# battery_current-meas.net
KiCad netlist of a schematic drawn in Altium Designer
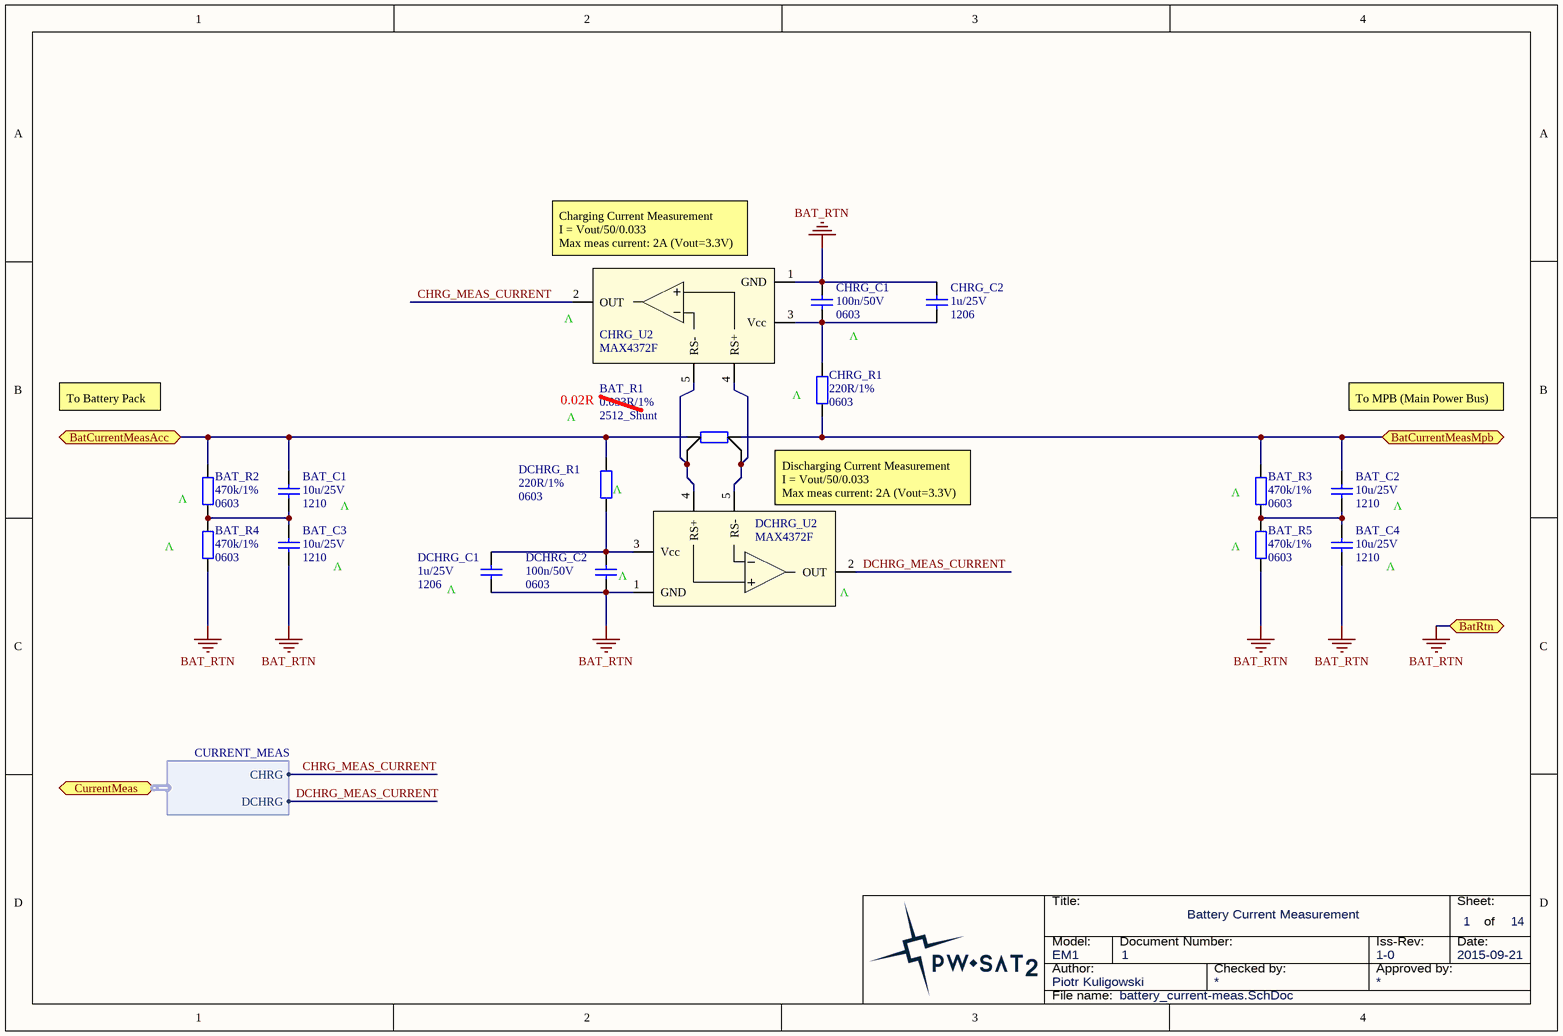
[diagram p0: battery_current-meas.SchDoc]

(export (version "E")
  (design (tool "Eeschema 10.0.6"))
  (components
    (comp (ref "BAT_C1")
      (value "10u/25V")
      (footprint "SMD_Capacitor_1210")
      (description "Ceramic Cap Murata Automotive 10u/25V X7R 1210")
      (fields
        (field (name "MANUFACTURER") "Murata")
        (field (name "MANUFACTURERPARTNUMBER") "GCJ32ER71E106KA12L")
        (field (name "PACKAGE") "1210")
      )
      (libsource (lib "capacitors") (part "Cer_GCJ32ER71E106KA12L"))
    )
    (comp (ref "BAT_C2")
      (value "10u/25V")
      (footprint "SMD_Capacitor_1210")
      (description "Ceramic Cap Murata Automotive 10u/25V X7R 1210")
      (fields
        (field (name "MANUFACTURER") "Murata")
        (field (name "MANUFACTURERPARTNUMBER") "GCJ32ER71E106KA12L")
        (field (name "PACKAGE") "1210")
      )
      (libsource (lib "capacitors") (part "Cer_GCJ32ER71E106KA12L"))
    )
    (comp (ref "BAT_C3")
      (value "10u/25V")
      (footprint "SMD_Capacitor_1210")
      (description "Ceramic Cap Murata Automotive 10u/25V X7R 1210")
      (fields
        (field (name "MANUFACTURER") "Murata")
        (field (name "MANUFACTURERPARTNUMBER") "GCJ32ER71E106KA12L")
        (field (name "PACKAGE") "1210")
      )
      (libsource (lib "capacitors") (part "Cer_GCJ32ER71E106KA12L"))
    )
    (comp (ref "BAT_C4")
      (value "10u/25V")
      (footprint "SMD_Capacitor_1210")
      (description "Ceramic Cap Murata Automotive 10u/25V X7R 1210")
      (fields
        (field (name "MANUFACTURER") "Murata")
        (field (name "MANUFACTURERPARTNUMBER") "GCJ32ER71E106KA12L")
        (field (name "PACKAGE") "1210")
      )
      (libsource (lib "capacitors") (part "Cer_GCJ32ER71E106KA12L"))
    )
    (comp (ref "BAT_R1")
      (value "0.033R/1%")
      (footprint "SMD_Resistor-shunt_2512")
      (description "33mR ,1%, 2W, shunt resistor, TE Connectivity.")
      (fields
        (field (name "MANUFACTURERPARTNUMBER") "LR2512-R033FW")
        (field (name "MANUFACTURER") "TE Connectivity")
        (field (name "PACKAGE") "2512_Shunt")
      )
      (libsource (lib "resistors") (part "LR2512-R033FW"))
    )
    (comp (ref "BAT_R2")
      (value "470k/1%")
      (footprint "SMD_Resistor_0603")
      (description "470k/1% Vishay CRCW 0603 Resistor. 100mW, 100ppm, 75V.")
      (fields
        (field (name "MANUFACTURER") "Vishay")
        (field (name "MANUFACTURERPARTNUMBER") "CRCW0603470KFKxxxx")
        (field (name "PACKAGE") "0603")
      )
      (libsource (lib "resistors") (part "CRCW0603470KFKxxxx"))
    )
    (comp (ref "BAT_R3")
      (value "470k/1%")
      (footprint "SMD_Resistor_0603")
      (description "470k/1% Vishay CRCW 0603 Resistor. 100mW, 100ppm, 75V.")
      (fields
        (field (name "MANUFACTURER") "Vishay")
        (field (name "MANUFACTURERPARTNUMBER") "CRCW0603470KFKxxxx")
        (field (name "PACKAGE") "0603")
      )
      (libsource (lib "resistors") (part "CRCW0603470KFKxxxx"))
    )
    (comp (ref "BAT_R4")
      (value "470k/1%")
      (footprint "SMD_Resistor_0603")
      (description "470k/1% Vishay CRCW 0603 Resistor. 100mW, 100ppm, 75V.")
      (fields
        (field (name "MANUFACTURER") "Vishay")
        (field (name "MANUFACTURERPARTNUMBER") "CRCW0603470KFKxxxx")
        (field (name "PACKAGE") "0603")
      )
      (libsource (lib "resistors") (part "CRCW0603470KFKxxxx"))
    )
    (comp (ref "BAT_R5")
      (value "470k/1%")
      (footprint "SMD_Resistor_0603")
      (description "470k/1% Vishay CRCW 0603 Resistor. 100mW, 100ppm, 75V.")
      (fields
        (field (name "MANUFACTURER") "Vishay")
        (field (name "MANUFACTURERPARTNUMBER") "CRCW0603470KFKxxxx")
        (field (name "PACKAGE") "0603")
      )
      (libsource (lib "resistors") (part "CRCW0603470KFKxxxx"))
    )
    (comp (ref "CHRG_C1")
      (value "100n/50V")
      (footprint "SMD_Capacitor_0603")
      (description "Ceramic Cap Murata Automotive 100n/50V X7R 0603")
      (fields
        (field (name "MANUFACTURER") "Murata")
        (field (name "MANUFACTURERPARTNUMBER") "GCJ188R71H104KA12D")
        (field (name "PACKAGE") "0603")
      )
      (libsource (lib "capacitors") (part "Cer_GCJ188R71H104KA12D"))
    )
    (comp (ref "CHRG_C2")
      (value "1u/25V")
      (footprint "SMD_Capacitor_1206")
      (description "Ceramic Cap Kemet COTS 1u/25V X7R 1206")
      (fields
        (field (name "MANUFACTURERPARTNUMBER") "C1206T105K3RALTU")
        (field (name "MANUFACTURER") "Kemet")
        (field (name "PACKAGE") "1206")
      )
      (libsource (lib "capacitors") (part "Cer_C1206T105K3RALTU"))
    )
    (comp (ref "CHRG_R1")
      (value "220R/1%")
      (footprint "SMD_Resistor_0603")
      (description "220R/1% Vishay CRCW 0603 Resistor. 100mW, 100ppm, 75V.")
      (fields
        (field (name "MANUFACTURERPARTNUMBER") "CRCW0603220RFKxxxx")
        (field (name "MANUFACTURER") "Vishay")
        (field (name "PACKAGE") "0603")
      )
      (libsource (lib "") (part "CRCW0603220RFKxxxx_1"))
    )
    (comp (ref "CHRG_U2")
      (value "MAX4372F")
      (footprint "SOT23-5")
      (description "High-Side Current-Sense Amplifier with Voltage Output")
      (fields (field (name "MANUFACTURER") "Maxim Integrated Products"))
      (libsource (lib "") (part "MAX4372_1"))
    )
    (comp (ref "DCHRG_C1")
      (value "1u/25V")
      (footprint "SMD_Capacitor_1206")
      (description "Ceramic Cap Kemet COTS 1u/25V X7R 1206")
      (fields
        (field (name "MANUFACTURERPARTNUMBER") "C1206T105K3RALTU")
        (field (name "MANUFACTURER") "Kemet")
        (field (name "PACKAGE") "1206")
      )
      (libsource (lib "capacitors") (part "Cer_C1206T105K3RALTU"))
    )
    (comp (ref "DCHRG_C2")
      (value "100n/50V")
      (footprint "SMD_Capacitor_0603")
      (description "Ceramic Cap Murata Automotive 100n/50V X7R 0603")
      (fields
        (field (name "MANUFACTURER") "Murata")
        (field (name "MANUFACTURERPARTNUMBER") "GCJ188R71H104KA12D")
        (field (name "PACKAGE") "0603")
      )
      (libsource (lib "capacitors") (part "Cer_GCJ188R71H104KA12D"))
    )
    (comp (ref "DCHRG_R1")
      (value "220R/1%")
      (footprint "SMD_Resistor_0603")
      (description "220R/1% Vishay CRCW 0603 Resistor. 100mW, 100ppm, 75V.")
      (fields
        (field (name "MANUFACTURERPARTNUMBER") "CRCW0603220RFKxxxx")
        (field (name "MANUFACTURER") "Vishay")
        (field (name "PACKAGE") "0603")
      )
      (libsource (lib "resistors") (part "CRCW0603220RFKxxxx"))
    )
    (comp (ref "DCHRG_U2")
      (value "MAX4372F")
      (footprint "SOT23-5")
      (description "High-Side Current-Sense Amplifier with Voltage Output")
      (fields (field (name "MANUFACTURER") "Maxim Integrated Products"))
      (libsource (lib "microcircuits") (part "MAX4372"))
    )
  )
  (nets
    (net (code "2") (name "/BatCurrentMeasAcc") (class "Default")
      (node (ref "BAT_C1") (pin "1") (pinfunction "1_1") (pintype "passive"))
      (node (ref "BAT_R1") (pin "1") (pinfunction "1_1") (pintype "passive"))
      (node (ref "BAT_R2") (pin "1") (pinfunction "1_1") (pintype "passive"))
      (node (ref "DCHRG_R1") (pin "1") (pinfunction "1_1") (pintype "passive"))
    )
    (net (code "3") (name "/BatCurrentMeasMpb") (class "Default")
      (node (ref "BAT_C2") (pin "1") (pinfunction "1_1") (pintype "passive"))
      (node (ref "BAT_R1") (pin "4") (pinfunction "4_4") (pintype "passive"))
      (node (ref "BAT_R3") (pin "1") (pinfunction "1_1") (pintype "passive"))
      (node (ref "CHRG_R1") (pin "1") (pinfunction "1_1") (pintype "passive"))
    )
    (net (code "4") (name "/CHRG_MEAS_CURRENT") (class "Default")
      (node (ref "CHRG_U2") (pin "2") (pinfunction "OUT_2") (pintype "passive"))
    )
    (net (code "5") (name "/DCHRG_MEAS_CURRENT") (class "Default")
      (node (ref "DCHRG_U2") (pin "2") (pinfunction "OUT_2") (pintype "passive"))
    )
    (net (code "7") (name "BAT_RTN") (class "Default")
      (node (ref "BAT_C3") (pin "2") (pinfunction "2_2") (pintype "passive"))
      (node (ref "BAT_C4") (pin "2") (pinfunction "2_2") (pintype "passive"))
      (node (ref "BAT_R4") (pin "2") (pinfunction "2_2") (pintype "passive"))
      (node (ref "BAT_R5") (pin "2") (pinfunction "2_2") (pintype "passive"))
      (node (ref "CHRG_C1") (pin "1") (pinfunction "1_1") (pintype "passive"))
      (node (ref "CHRG_C2") (pin "1") (pinfunction "1_1") (pintype "passive"))
      (node (ref "CHRG_U2") (pin "1") (pinfunction "GND_1") (pintype "passive"))
      (node (ref "DCHRG_C1") (pin "2") (pinfunction "2_2") (pintype "passive"))
      (node (ref "DCHRG_C2") (pin "2") (pinfunction "2_2") (pintype "passive"))
      (node (ref "DCHRG_U2") (pin "1") (pinfunction "GND_1") (pintype "passive"))
    )
    (net (code "8") (name "Net-(BAT_C1-Pad2)") (class "Default")
      (node (ref "BAT_C1") (pin "2") (pinfunction "2_2") (pintype "passive"))
      (node (ref "BAT_C3") (pin "1") (pinfunction "1_1") (pintype "passive"))
      (node (ref "BAT_R2") (pin "2") (pinfunction "2_2") (pintype "passive"))
      (node (ref "BAT_R4") (pin "1") (pinfunction "1_1") (pintype "passive"))
    )
    (net (code "9") (name "Net-(BAT_C2-Pad2)") (class "Default")
      (node (ref "BAT_C2") (pin "2") (pinfunction "2_2") (pintype "passive"))
      (node (ref "BAT_C4") (pin "1") (pinfunction "1_1") (pintype "passive"))
      (node (ref "BAT_R3") (pin "2") (pinfunction "2_2") (pintype "passive"))
      (node (ref "BAT_R5") (pin "1") (pinfunction "1_1") (pintype "passive"))
    )
    (net (code "10") (name "Net-(CHRG_U2-RS+)") (class "Default")
      (node (ref "BAT_R1") (pin "3") (pinfunction "3_3") (pintype "passive"))
      (node (ref "CHRG_U2") (pin "4") (pinfunction "RS+_4") (pintype "passive"))
      (node (ref "DCHRG_U2") (pin "5") (pinfunction "RS-_5") (pintype "passive"))
    )
    (net (code "11") (name "Net-(CHRG_U2-RS-)") (class "Default")
      (node (ref "BAT_R1") (pin "2") (pinfunction "2_2") (pintype "passive"))
      (node (ref "CHRG_U2") (pin "5") (pinfunction "RS-_5") (pintype "passive"))
      (node (ref "DCHRG_U2") (pin "4") (pinfunction "RS+_4") (pintype "passive"))
    )
    (net (code "12") (name "Net-(CHRG_U2-Vcc)") (class "Default")
      (node (ref "CHRG_C1") (pin "2") (pinfunction "2_2") (pintype "passive"))
      (node (ref "CHRG_C2") (pin "2") (pinfunction "2_2") (pintype "passive"))
      (node (ref "CHRG_R1") (pin "2") (pinfunction "2_2") (pintype "passive"))
      (node (ref "CHRG_U2") (pin "3") (pinfunction "Vcc_3") (pintype "passive"))
    )
    (net (code "13") (name "Net-(DCHRG_U2-Vcc)") (class "Default")
      (node (ref "DCHRG_C1") (pin "1") (pinfunction "1_1") (pintype "passive"))
      (node (ref "DCHRG_C2") (pin "1") (pinfunction "1_1") (pintype "passive"))
      (node (ref "DCHRG_R1") (pin "2") (pinfunction "2_2") (pintype "passive"))
      (node (ref "DCHRG_U2") (pin "3") (pinfunction "Vcc_3") (pintype "passive"))
    )
  )
)
